# 9-Other_Inputs.net
KiCad netlist of a schematic drawn in Altium Designer
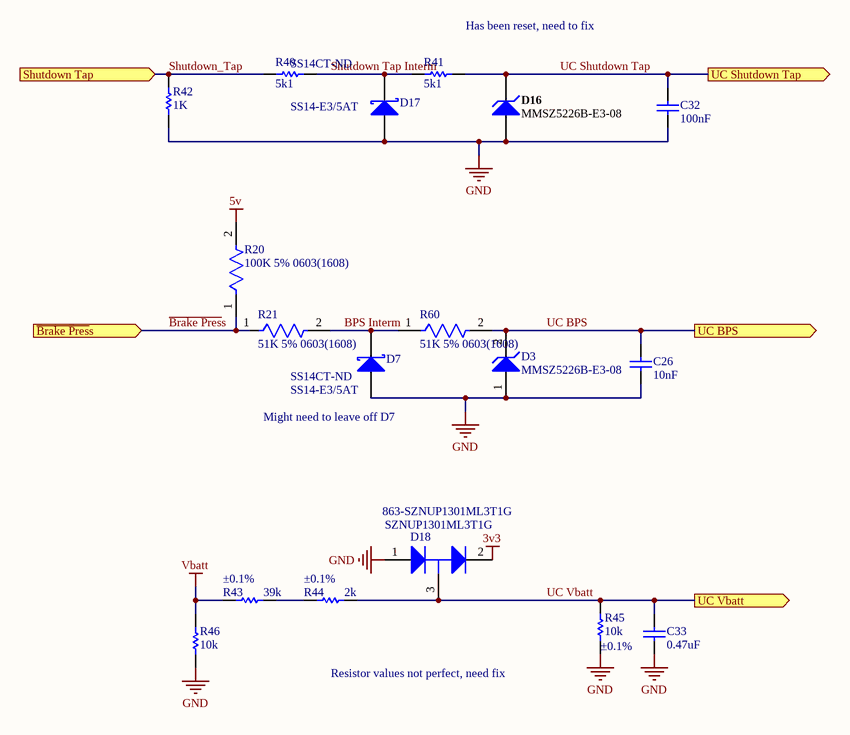
[diagram p0: 9-Other_Inputs.SchDoc]

(export (version "E")
  (design (tool "Eeschema 10.0.6"))
  (components
    (comp (ref "C26")
      (value "10nF")
      (footprint "1608[0603]")
      (description "Capacitor")
      (fields
        (field (name "MANUFACTURER") "Yageo")
        (field (name "MANUFACTURER PART NUMBER") "CC0603KRX7R9BB104")
      )
      (libsource (lib "Miscellaneous Devices") (part "Cap"))
    )
    (comp (ref "C32")
      (value "100nF")
      (footprint "1608[0603]")
      (description "Capacitor")
      (fields
        (field (name "MANUFACTURER") "Yageo")
        (field (name "MANUFACTURER PART NUMBER") "CC0603KRX7R9BB102")
      )
      (libsource (lib "Miscellaneous Devices") (part "Cap"))
    )
    (comp (ref "C33")
      (value "0.47uF")
      (footprint "1608[0603]")
      (description "Capacitor")
      (fields
        (field (name "MANUFACTURER") "Yageo")
        (field (name "MANUFACTURER PART NUMBER") "CC0603KRX7R8BB474")
      )
      (libsource (lib "Miscellaneous Devices") (part "Cap"))
    )
    (comp (ref "D3")
      (value "MMSZ5226B-E3-08")
      (footprint "VISH-SOD-123-2_V")
      (description "Zener Voltage Regulator, 500 mW, 2-Pin SOD-123, Pb-Free, Tape and Reel")
      (fields (field (name "PARTNUMBER") "MMSZ3V6T1G") (field (name "MANUFACTURER") "On Semiconductor"))
      (libsource (lib "Altium Content Vault") (part "ONSC-K1A2-2"))
    )
    (comp (ref "D7")
      (value "SS14-E3/5AT")
      (footprint "VISH-DO-214AC-2_V")
      (fields
        (field (name "MANUFACTURER") "Vishay Semiconductor")
        (field (name "SUPPLIER PART NUMBER 1") "SS14CT-ND")
      )
      (libsource (lib "Altium Content Vault") (part "VISH-DSKY_A1K2-2"))
    )
    (comp (ref "D16")
      (value "MMSZ5226B-E3-08")
      (footprint "VISH-SOD-123-2_V")
      (description "Small Signal Zener Diode, 3.3 V +/- 5%, -55 to 155 degC, 2-Pin SOD-123, RoHS, Tape and Reel")
      (fields (field (name "TOLERANCE") "+/- 5%") (field (name "MANUFACTURER") "Vishay Semiconductor"))
      (libsource (lib "Altium Content Vault") (part "VISH-DZEN_A1K2-2"))
    )
    (comp (ref "D17")
      (value "SS14-E3/5AT")
      (footprint "VISH-DO-214AC-2_V")
      (fields
        (field (name "MANUFACTURER") "Vishay Semiconductor")
        (field (name "SUPPLIER PART NUMBER 1") "SS14CT-ND")
      )
      (libsource (lib "Altium Content Vault") (part "VISH-DSKY_A1K2-2"))
    )
    (comp (ref "D18")
      (value "SZNUP1301ML3T1G")
      (footprint "ONSC-SOT-23-3-318-08_V")
      (fields
        (field (name "MANUFACTURER") "On Semiconductor")
        (field (name "SUPPLIER PART NUMBER 1") "863-SZNUP1301ML3T1G")
      )
      (libsource (lib "Altium Content Vault") (part "ONSC-NUP1301-SOT-23-3-318-08"))
    )
    (comp (ref "R20")
      (value "100K 5% 0603(1608)")
      (footprint "RESC0603(1608)_N")
      (description "10kΩ ±5% 0.1W 0603 Thick Film Chip Resistor AEC-Q200 compliant")
      (fields (field (name "TOLERANCE") "5%"))
      (libsource (lib "Altium Content Vault") (part "1029c3af85768c4190bb7ad29bc67b5"))
    )
    (comp (ref "R21")
      (value "51K 5% 0603(1608)")
      (footprint "RESC0603(1608)_N")
      (description "10kΩ ±5% 0.1W 0603 Thick Film Chip Resistor AEC-Q200 compliant")
      (fields (field (name "TOLERANCE") "5%"))
      (libsource (lib "Altium Content Vault") (part "1029c3af85768c4190bb7ad29bc67b5"))
    )
    (comp (ref "R40")
      (value "5k1")
      (footprint "1608[0603]")
      (description "Resistor")
      (fields
        (field (name "MANUFACTURER") "Panasonic Electronic Components")
        (field (name "MANUFACTURER PART NUMBER") "ERJ-PA3F1001V")
      )
      (libsource (lib "Miscellaneous Devices") (part "Res1"))
    )
    (comp (ref "R41")
      (value "5k1")
      (footprint "1608[0603]")
      (description "Resistor")
      (fields
        (field (name "MANUFACTURER") "Panasonic Electronic Components")
        (field (name "MANUFACTURER PART NUMBER") "ERJ-PA3F1001V")
      )
      (libsource (lib "Miscellaneous Devices") (part "Res1"))
    )
    (comp (ref "R42")
      (value "1K")
      (footprint "1608[0603]")
      (description "Resistor")
      (fields
        (field (name "MANUFACTURER") "Panasonic Electronic Components")
        (field (name "MANUFACTURER PART NUMBER") "ERJ-PA3F1001V")
      )
      (libsource (lib "Miscellaneous Devices") (part "Res1"))
    )
    (comp (ref "R43")
      (value "39k")
      (footprint "1608[0603]")
      (description "Resistor")
      (fields
        (field (name "MANUFACTURER") "Yageo")
        (field (name "MANUFACTURER PART NUMBER") "RT0603BRD0739KL")
        (field (name "TOLERANCE") "±0.1%")
      )
      (libsource (lib "Miscellaneous Devices") (part "Res1"))
    )
    (comp (ref "R44")
      (value "2k")
      (footprint "1608[0603]")
      (description "Resistor")
      (fields
        (field (name "MANUFACTURER") "Yageo")
        (field (name "MANUFACTURER PART NUMBER") "AT0603BRD072KL")
        (field (name "TOLERANCE") "±0.1%")
      )
      (libsource (lib "Miscellaneous Devices") (part "Res1"))
    )
    (comp (ref "R45")
      (value "10k")
      (footprint "1608[0603]")
      (description "Resistor")
      (fields
        (field (name "MANUFACTURER") "Yageo")
        (field (name "MANUFACTURER PART NUMBER") "RT0603BRD0710KL")
        (field (name "TOLERANCE") "±0.1%")
      )
      (libsource (lib "Miscellaneous Devices") (part "Res1"))
    )
    (comp (ref "R46")
      (value "10k")
      (footprint "1608[0603]")
      (description "Resistor")
      (fields
        (field (name "MANUFACTURER") "Yageo")
        (field (name "MANUFACTURER PART NUMBER") "RC0603JR-0710KL")
      )
      (libsource (lib "Miscellaneous Devices") (part "Res1"))
    )
    (comp (ref "R60")
      (value "51K 5% 0603(1608)")
      (footprint "RESC0603(1608)_N")
      (description "10kΩ ±5% 0.1W 0603 Thick Film Chip Resistor AEC-Q200 compliant")
      (fields (field (name "TOLERANCE") "5%"))
      (libsource (lib "Altium Content Vault") (part "1029c3af85768c4190bb7ad29bc67b5"))
    )
  )
  (nets
    (net (code "1") (name "/BPS Interm") (class "Default")
      (node (ref "D7") (pin "2") (pinfunction "K_2") (pintype "passive"))
      (node (ref "R21") (pin "2") (pinfunction "2_2") (pintype "passive"))
      (node (ref "R60") (pin "1") (pinfunction "1_1") (pintype "passive"))
    )
    (net (code "2") (name "/Shutdown Tap Interm") (class "Default")
      (node (ref "D17") (pin "2") (pinfunction "K_2") (pintype "passive"))
      (node (ref "R40") (pin "1") (pinfunction "1_1") (pintype "passive"))
      (node (ref "R41") (pin "2") (pinfunction "2_2") (pintype "passive"))
    )
    (net (code "3") (name "/Shutdown_Tap") (class "Default")
      (node (ref "R40") (pin "2") (pinfunction "2_2") (pintype "passive"))
      (node (ref "R42") (pin "2") (pinfunction "2_2") (pintype "passive"))
    )
    (net (code "4") (name "/UC BPS") (class "Default")
      (node (ref "C26") (pin "2") (pinfunction "2_2") (pintype "passive"))
      (node (ref "D3") (pin "2") (pinfunction "A_2") (pintype "passive"))
      (node (ref "R60") (pin "2") (pinfunction "2_2") (pintype "passive"))
    )
    (net (code "5") (name "/UC Shutdown Tap") (class "Default")
      (node (ref "C32") (pin "2") (pinfunction "2_2") (pintype "passive"))
      (node (ref "D16") (pin "2") (pinfunction "K_2") (pintype "passive"))
      (node (ref "R41") (pin "1") (pinfunction "1_1") (pintype "passive"))
    )
    (net (code "6") (name "/UC Vbatt") (class "Default")
      (node (ref "C33") (pin "2") (pinfunction "2_2") (pintype "passive"))
      (node (ref "D18") (pin "3") (pinfunction "K/A_3") (pintype "passive"))
      (node (ref "R44") (pin "2") (pinfunction "2_2") (pintype "passive"))
      (node (ref "R45") (pin "2") (pinfunction "2_2") (pintype "passive"))
    )
    (net (code "7") (name "/~{Brake Pres}s") (class "Default")
      (node (ref "R20") (pin "1") (pinfunction "1_1") (pintype "passive"))
      (node (ref "R21") (pin "1") (pinfunction "1_1") (pintype "passive"))
    )
    (net (code "8") (name "3v3") (class "Default")
      (node (ref "D18") (pin "2") (pinfunction "K_2") (pintype "passive"))
    )
    (net (code "9") (name "5v") (class "Default")
      (node (ref "R20") (pin "2") (pinfunction "2_2") (pintype "passive"))
    )
    (net (code "10") (name "GND") (class "Default")
      (node (ref "C26") (pin "1") (pinfunction "1_1") (pintype "passive"))
      (node (ref "C32") (pin "1") (pinfunction "1_1") (pintype "passive"))
      (node (ref "C33") (pin "1") (pinfunction "1_1") (pintype "passive"))
      (node (ref "D16") (pin "1") (pinfunction "A_1") (pintype "passive"))
      (node (ref "D17") (pin "1") (pinfunction "A_1") (pintype "passive"))
      (node (ref "D18") (pin "1") (pinfunction "A_1") (pintype "passive"))
      (node (ref "D3") (pin "1") (pinfunction "K_1") (pintype "passive"))
      (node (ref "D7") (pin "1") (pinfunction "A_1") (pintype "passive"))
      (node (ref "R42") (pin "1") (pinfunction "1_1") (pintype "passive"))
      (node (ref "R45") (pin "1") (pinfunction "1_1") (pintype "passive"))
      (node (ref "R46") (pin "1") (pinfunction "1_1") (pintype "passive"))
    )
    (net (code "11") (name "Net-(R43-Pad2)") (class "Default")
      (node (ref "R43") (pin "2") (pinfunction "2_2") (pintype "passive"))
      (node (ref "R44") (pin "1") (pinfunction "1_1") (pintype "passive"))
    )
    (net (code "12") (name "Vbatt") (class "Default")
      (node (ref "R43") (pin "1") (pinfunction "1_1") (pintype "passive"))
      (node (ref "R46") (pin "2") (pinfunction "2_2") (pintype "passive"))
    )
  )
)
